# UsbAsp_IR-Gross-24.net
KiCad netlist of a schematic drawn in EAGLE
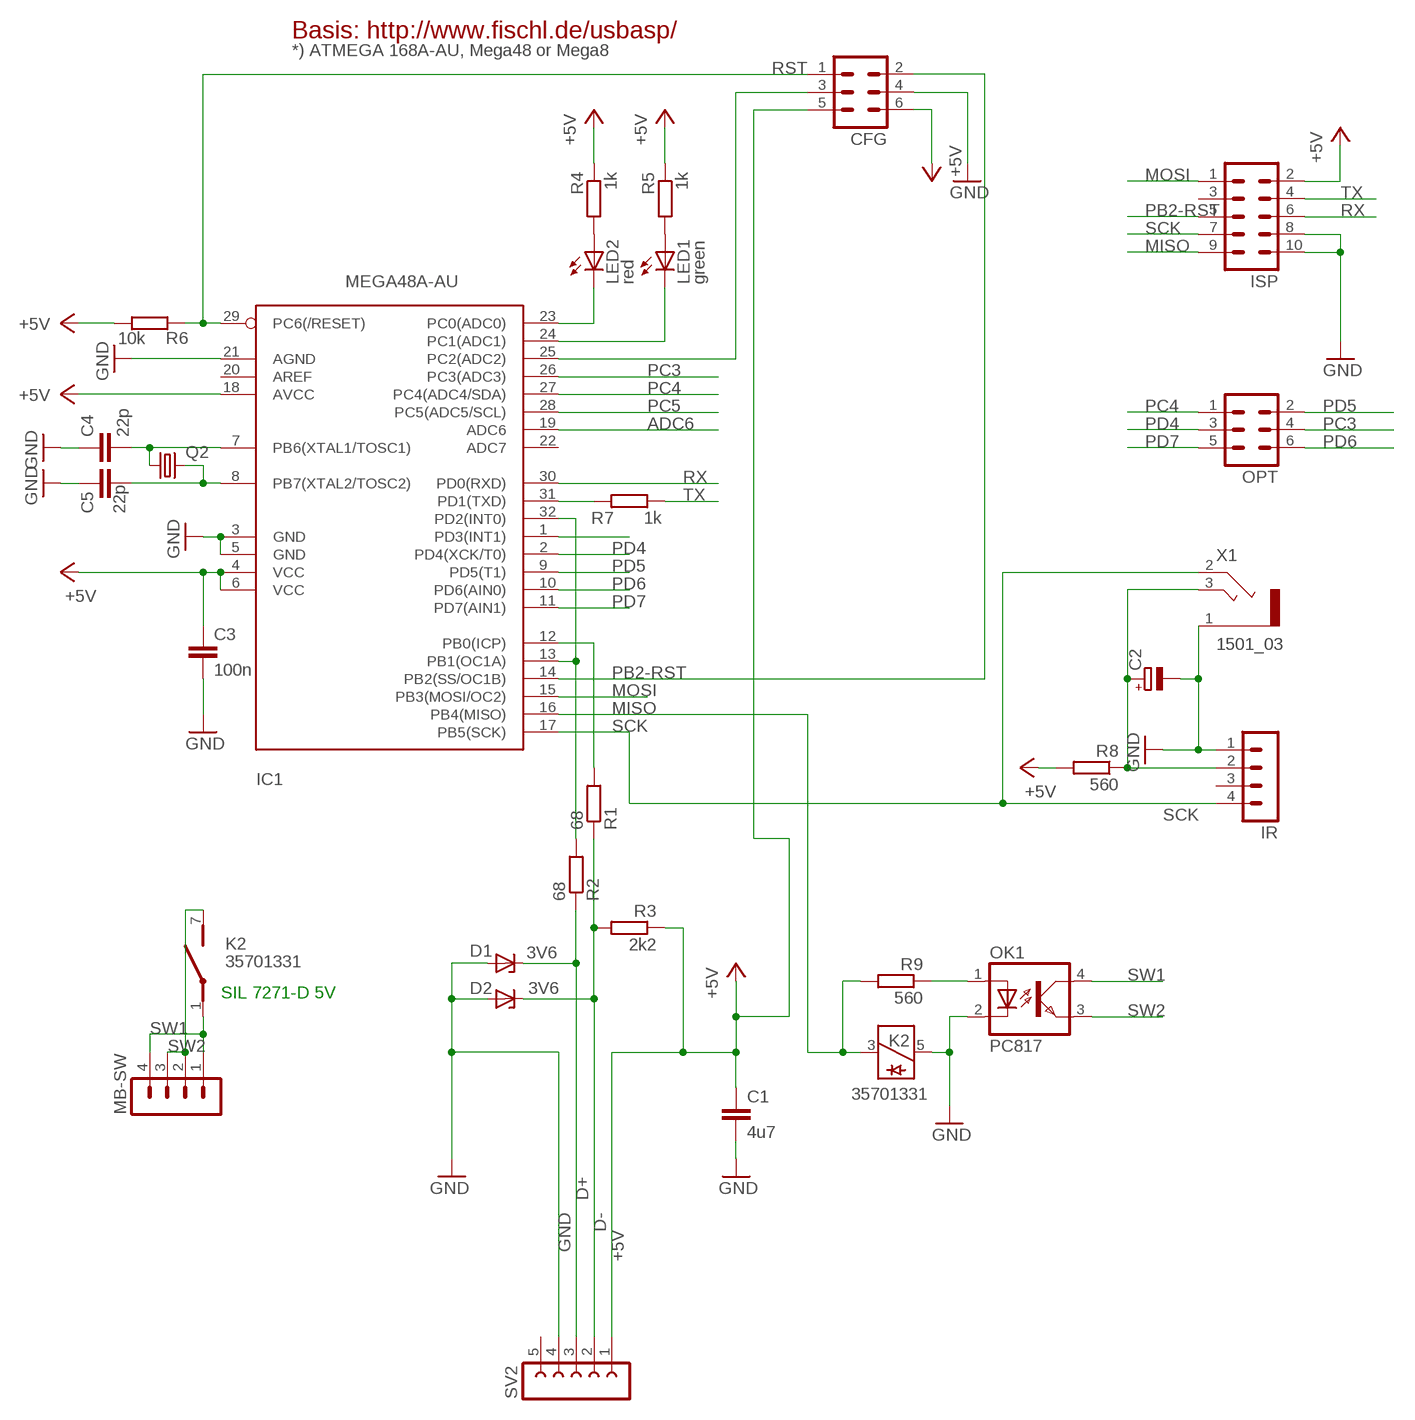
[diagram p0: schematic, sheet 1]

(export (version "E")
  (design (tool "Eeschema 10.0.6"))
  (components
    (comp (ref "C1")
      (value "4u7")
      (footprint "eagle-import:C0805")
      (libsource (lib "eagle-import") (part "C-EUC0805"))
    )
    (comp (ref "C2")
      (value "CPOL-EU085CS-1AR")
      (footprint "eagle-import:085CS_1AR")
      (libsource (lib "eagle-import") (part "CPOL-EU085CS-1AR"))
    )
    (comp (ref "C3")
      (value "100n")
      (footprint "eagle-import:C0805")
      (libsource (lib "eagle-import") (part "C-EUC0805"))
    )
    (comp (ref "C4")
      (value "22p")
      (footprint "eagle-import:C0805")
      (libsource (lib "eagle-import") (part "C-EUC0805"))
    )
    (comp (ref "C5")
      (value "22p")
      (footprint "eagle-import:C0805")
      (libsource (lib "eagle-import") (part "C-EUC0805"))
    )
    (comp (ref "CFG")
      (value "MA03-2")
      (footprint "eagle-import:MA03-2")
      (libsource (lib "eagle-import") (part "MA03-2"))
    )
    (comp (ref "D1")
      (value "3V6")
      (footprint "eagle-import:SOD80C")
      (libsource (lib "eagle-import") (part "ZENER-DIODESOD80C"))
    )
    (comp (ref "D2")
      (value "3V6")
      (footprint "eagle-import:SOD80C")
      (libsource (lib "eagle-import") (part "ZENER-DIODESOD80C"))
    )
    (comp (ref "IC1")
      (value "MEGA48A-AU")
      (footprint "eagle-import:TQFP32-08")
      (libsource (lib "eagle-import") (part "MEGA8-AI"))
    )
    (comp (ref "IR")
      (value "MA04-1")
      (footprint "eagle-import:MA04-1")
      (libsource (lib "eagle-import") (part "MA04-1"))
    )
    (comp (ref "ISP")
      (value "MA05-2")
      (footprint "eagle-import:MA05-2")
      (libsource (lib "eagle-import") (part "MA05-2"))
    )
    (comp (ref "K2")
      (value "35701331")
      (footprint "eagle-import:REED")
      (libsource (lib "eagle-import") (part "35701331"))
    )
    (comp (ref "LED1")
      (value "green")
      (footprint "eagle-import:CHIPLED_1206")
      (libsource (lib "eagle-import") (part "LEDCHIPLED_1206"))
    )
    (comp (ref "LED2")
      (value "red")
      (footprint "eagle-import:CHIPLED_1206")
      (libsource (lib "eagle-import") (part "LEDCHIPLED_1206"))
    )
    (comp (ref "MB-SW")
      (value "MA04-1")
      (footprint "eagle-import:MA04-1")
      (libsource (lib "eagle-import") (part "MA04-1"))
    )
    (comp (ref "OK1")
      (value "PC817")
      (footprint "eagle-import:DIL04")
      (fields (field (name "MPN") "PC817X4J000F"))
      (libsource (lib "eagle-import") (part "PC817"))
    )
    (comp (ref "OPT")
      (value "MA03-2")
      (footprint "eagle-import:MA03-2")
      (libsource (lib "eagle-import") (part "MA03-2"))
    )
    (comp (ref "Q2")
      (value "CRYSTALHC49UP")
      (footprint "eagle-import:HC49UP")
      (libsource (lib "eagle-import") (part "CRYSTALHC49UP"))
    )
    (comp (ref "R1")
      (value "68")
      (footprint "eagle-import:M0805")
      (libsource (lib "eagle-import") (part "R-EU_M0805"))
    )
    (comp (ref "R2")
      (value "68")
      (footprint "eagle-import:M0805")
      (libsource (lib "eagle-import") (part "R-EU_M0805"))
    )
    (comp (ref "R3")
      (value "2k2")
      (footprint "eagle-import:M0805")
      (libsource (lib "eagle-import") (part "R-EU_M0805"))
    )
    (comp (ref "R4")
      (value "1k")
      (footprint "eagle-import:M0805")
      (libsource (lib "eagle-import") (part "R-EU_M0805"))
    )
    (comp (ref "R5")
      (value "1k")
      (footprint "eagle-import:M0805")
      (libsource (lib "eagle-import") (part "R-EU_M0805"))
    )
    (comp (ref "R6")
      (value "10k")
      (footprint "eagle-import:M0805")
      (libsource (lib "eagle-import") (part "R-EU_M0805"))
    )
    (comp (ref "R7")
      (value "1k")
      (footprint "eagle-import:M0805")
      (libsource (lib "eagle-import") (part "R-EU_M0805"))
    )
    (comp (ref "R8")
      (value "560")
      (footprint "eagle-import:M0805")
      (libsource (lib "eagle-import") (part "R-EU_M0805"))
    )
    (comp (ref "R9")
      (value "560")
      (footprint "eagle-import:M0805")
      (libsource (lib "eagle-import") (part "R-EU_M0805"))
    )
    (comp (ref "SV2")
      (value "FE05W")
      (footprint "eagle-import:FE05W")
      (libsource (lib "eagle-import") (part "FE05W"))
    )
    (comp (ref "X1")
      (value "1501_03")
      (footprint "eagle-import:1501_03")
      (libsource (lib "eagle-import") (part "1501_03"))
    )
  )
  (nets
    (net (code "1") (name "+5V") (class "Default")
      (node (ref "C1") (pin "1") (pinfunction "1_1") (pintype "passive"))
      (node (ref "C3") (pin "1") (pinfunction "1_1") (pintype "passive"))
      (node (ref "CFG") (pin "5") (pinfunction "5_5") (pintype "passive"))
      (node (ref "CFG") (pin "6") (pinfunction "6_6") (pintype "passive"))
      (node (ref "IC1") (pin "18") (pinfunction "AVCC_18") (pintype "power_in"))
      (node (ref "IC1") (pin "4") (pinfunction "VCC_4") (pintype "power_in"))
      (node (ref "IC1") (pin "6") (pinfunction "VCC_6") (pintype "power_in"))
      (node (ref "ISP") (pin "2") (pinfunction "2_2") (pintype "passive"))
      (node (ref "R3") (pin "1") (pinfunction "1_1") (pintype "passive"))
      (node (ref "R4") (pin "1") (pinfunction "1_1") (pintype "passive"))
      (node (ref "R5") (pin "1") (pinfunction "1_1") (pintype "passive"))
      (node (ref "R6") (pin "1") (pinfunction "1_1") (pintype "passive"))
      (node (ref "R8") (pin "2") (pinfunction "2_2") (pintype "passive"))
      (node (ref "SV2") (pin "1") (pinfunction "1_1") (pintype "passive"))
    )
    (net (code "2") (name "/ADC6") (class "Default")
      (node (ref "IC1") (pin "19") (pinfunction "ADC6_19") (pintype "bidirectional"))
    )
    (net (code "3") (name "/D+") (class "Default")
      (node (ref "D1") (pin "C") (pinfunction "C_C") (pintype "passive"))
      (node (ref "R2") (pin "1") (pinfunction "1_1") (pintype "passive"))
      (node (ref "SV2") (pin "3") (pinfunction "3_3") (pintype "passive"))
    )
    (net (code "4") (name "/D-") (class "Default")
      (node (ref "D2") (pin "C") (pinfunction "C_C") (pintype "passive"))
      (node (ref "R1") (pin "1") (pinfunction "1_1") (pintype "passive"))
      (node (ref "R3") (pin "2") (pinfunction "2_2") (pintype "passive"))
      (node (ref "SV2") (pin "2") (pinfunction "2_2") (pintype "passive"))
    )
    (net (code "5") (name "/MISO") (class "Default")
      (node (ref "IC1") (pin "16") (pinfunction "PB4(MISO)_16") (pintype "bidirectional"))
      (node (ref "ISP") (pin "9") (pinfunction "9_9") (pintype "passive"))
      (node (ref "K2") (pin "3") (pinfunction "3_3") (pintype "passive"))
      (node (ref "R9") (pin "2") (pinfunction "2_2") (pintype "passive"))
    )
    (net (code "6") (name "/MOSI") (class "Default")
      (node (ref "IC1") (pin "15") (pinfunction "PB3(MOSI/OC2)_15") (pintype "bidirectional"))
      (node (ref "ISP") (pin "1") (pinfunction "1_1") (pintype "passive"))
    )
    (net (code "7") (name "/PB2-RST") (class "Default")
      (node (ref "CFG") (pin "2") (pinfunction "2_2") (pintype "passive"))
      (node (ref "IC1") (pin "14") (pinfunction "PB2(SS/OC1B)_14") (pintype "bidirectional"))
      (node (ref "ISP") (pin "5") (pinfunction "5_5") (pintype "passive"))
    )
    (net (code "8") (name "/PC3") (class "Default")
      (node (ref "IC1") (pin "26") (pinfunction "PC3(ADC3)_26") (pintype "bidirectional"))
      (node (ref "OPT") (pin "4") (pinfunction "4_4") (pintype "passive"))
    )
    (net (code "9") (name "/PC4") (class "Default")
      (node (ref "IC1") (pin "27") (pinfunction "PC4(ADC4/SDA)_27") (pintype "bidirectional"))
      (node (ref "OPT") (pin "1") (pinfunction "1_1") (pintype "passive"))
    )
    (net (code "10") (name "/PC5") (class "Default")
      (node (ref "IC1") (pin "28") (pinfunction "PC5(ADC5/SCL)_28") (pintype "bidirectional"))
    )
    (net (code "11") (name "/PD4") (class "Default")
      (node (ref "IC1") (pin "2") (pinfunction "PD4(XCK/T0)_2") (pintype "bidirectional"))
      (node (ref "OPT") (pin "3") (pinfunction "3_3") (pintype "passive"))
    )
    (net (code "12") (name "/PD5") (class "Default")
      (node (ref "IC1") (pin "9") (pinfunction "PD5(T1)_9") (pintype "bidirectional"))
      (node (ref "OPT") (pin "2") (pinfunction "2_2") (pintype "passive"))
    )
    (net (code "13") (name "/PD6") (class "Default")
      (node (ref "IC1") (pin "10") (pinfunction "PD6(AIN0)_10") (pintype "bidirectional"))
      (node (ref "OPT") (pin "6") (pinfunction "6_6") (pintype "passive"))
    )
    (net (code "14") (name "/PD7") (class "Default")
      (node (ref "IC1") (pin "11") (pinfunction "PD7(AIN1)_11") (pintype "bidirectional"))
      (node (ref "OPT") (pin "5") (pinfunction "5_5") (pintype "passive"))
    )
    (net (code "15") (name "/RST") (class "Default")
      (node (ref "CFG") (pin "1") (pinfunction "1_1") (pintype "passive"))
      (node (ref "IC1") (pin "29") (pinfunction "PC6(/RESET)_29") (pintype "bidirectional"))
      (node (ref "R6") (pin "2") (pinfunction "2_2") (pintype "passive"))
    )
    (net (code "16") (name "/RX") (class "Default")
      (node (ref "IC1") (pin "30") (pinfunction "PD0(RXD)_30") (pintype "bidirectional"))
      (node (ref "ISP") (pin "6") (pinfunction "6_6") (pintype "passive"))
    )
    (net (code "17") (name "/SCK") (class "Default")
      (node (ref "IC1") (pin "17") (pinfunction "PB5(SCK)_17") (pintype "bidirectional"))
      (node (ref "IR") (pin "4") (pinfunction "4_4") (pintype "passive"))
      (node (ref "ISP") (pin "7") (pinfunction "7_7") (pintype "passive"))
      (node (ref "X1") (pin "2") (pinfunction "2_2") (pintype "passive"))
    )
    (net (code "18") (name "/SW1") (class "Default")
      (node (ref "K2") (pin "1") (pinfunction "P_1") (pintype "passive"))
      (node (ref "MB-SW") (pin "1") (pinfunction "1_1") (pintype "passive"))
      (node (ref "MB-SW") (pin "4") (pinfunction "4_4") (pintype "passive"))
      (node (ref "OK1") (pin "4") (pinfunction "COL_4") (pintype "passive"))
    )
    (net (code "19") (name "/SW2") (class "Default")
      (node (ref "K2") (pin "7") (pinfunction "S_7") (pintype "passive"))
      (node (ref "MB-SW") (pin "2") (pinfunction "2_2") (pintype "passive"))
      (node (ref "MB-SW") (pin "3") (pinfunction "3_3") (pintype "passive"))
      (node (ref "OK1") (pin "3") (pinfunction "EMIT_3") (pintype "passive"))
    )
    (net (code "20") (name "/TX") (class "Default")
      (node (ref "ISP") (pin "4") (pinfunction "4_4") (pintype "passive"))
      (node (ref "R7") (pin "1") (pinfunction "1_1") (pintype "passive"))
    )
    (net (code "21") (name "GND") (class "Default")
      (node (ref "C1") (pin "2") (pinfunction "2_2") (pintype "passive"))
      (node (ref "C2") (pin "-") (pinfunction "-_-") (pintype "passive"))
      (node (ref "C3") (pin "2") (pinfunction "2_2") (pintype "passive"))
      (node (ref "C4") (pin "1") (pinfunction "1_1") (pintype "passive"))
      (node (ref "C5") (pin "1") (pinfunction "1_1") (pintype "passive"))
      (node (ref "CFG") (pin "4") (pinfunction "4_4") (pintype "passive"))
      (node (ref "D1") (pin "A") (pinfunction "A_A") (pintype "passive"))
      (node (ref "D2") (pin "A") (pinfunction "A_A") (pintype "passive"))
      (node (ref "IC1") (pin "21") (pinfunction "AGND_21") (pintype "power_in"))
      (node (ref "IC1") (pin "3") (pinfunction "GND_3") (pintype "power_in"))
      (node (ref "IC1") (pin "5") (pinfunction "GND_5") (pintype "power_in"))
      (node (ref "IR") (pin "1") (pinfunction "1_1") (pintype "passive"))
      (node (ref "ISP") (pin "10") (pinfunction "10_10") (pintype "passive"))
      (node (ref "ISP") (pin "8") (pinfunction "8_8") (pintype "passive"))
      (node (ref "K2") (pin "5") (pinfunction "5_5") (pintype "passive"))
      (node (ref "OK1") (pin "2") (pinfunction "C_2") (pintype "passive"))
      (node (ref "SV2") (pin "4") (pinfunction "4_4") (pintype "passive"))
      (node (ref "X1") (pin "1") (pinfunction "1_1") (pintype "passive"))
    )
    (net (code "22") (name "Net-(C2-Pad+)") (class "Default")
      (node (ref "C2") (pin "+") (pinfunction "+_+") (pintype "passive"))
      (node (ref "IR") (pin "2") (pinfunction "2_2") (pintype "passive"))
      (node (ref "R8") (pin "1") (pinfunction "1_1") (pintype "passive"))
      (node (ref "X1") (pin "3") (pinfunction "3_3") (pintype "passive"))
    )
    (net (code "23") (name "Net-(IC1-PB0(ICP))") (class "Default")
      (node (ref "IC1") (pin "12") (pinfunction "PB0(ICP)_12") (pintype "bidirectional"))
      (node (ref "R1") (pin "2") (pinfunction "2_2") (pintype "passive"))
    )
    (net (code "24") (name "Net-(IC1-PB1(OC1A))") (class "Default")
      (node (ref "IC1") (pin "13") (pinfunction "PB1(OC1A)_13") (pintype "bidirectional"))
      (node (ref "IC1") (pin "32") (pinfunction "PD2(INT0)_32") (pintype "bidirectional"))
      (node (ref "R2") (pin "2") (pinfunction "2_2") (pintype "passive"))
    )
    (net (code "25") (name "Net-(IC1-PB6(XTAL1{slash}TOSC1))") (class "Default")
      (node (ref "C4") (pin "2") (pinfunction "2_2") (pintype "passive"))
      (node (ref "IC1") (pin "7") (pinfunction "PB6(XTAL1/TOSC1)_7") (pintype "bidirectional"))
      (node (ref "Q2") (pin "1") (pinfunction "1_1") (pintype "passive"))
    )
    (net (code "26") (name "Net-(IC1-PB7(XTAL2{slash}TOSC2))") (class "Default")
      (node (ref "C5") (pin "2") (pinfunction "2_2") (pintype "passive"))
      (node (ref "IC1") (pin "8") (pinfunction "PB7(XTAL2/TOSC2)_8") (pintype "bidirectional"))
      (node (ref "Q2") (pin "2") (pinfunction "2_2") (pintype "passive"))
    )
    (net (code "27") (name "Net-(IC1-PC0(ADC0))") (class "Default")
      (node (ref "IC1") (pin "23") (pinfunction "PC0(ADC0)_23") (pintype "bidirectional"))
      (node (ref "LED2") (pin "C") (pinfunction "C_C") (pintype "passive"))
    )
    (net (code "28") (name "Net-(IC1-PC1(ADC1))") (class "Default")
      (node (ref "IC1") (pin "24") (pinfunction "PC1(ADC1)_24") (pintype "bidirectional"))
      (node (ref "LED1") (pin "C") (pinfunction "C_C") (pintype "passive"))
    )
    (net (code "29") (name "Net-(IC1-PC2(ADC2))") (class "Default")
      (node (ref "CFG") (pin "3") (pinfunction "3_3") (pintype "passive"))
      (node (ref "IC1") (pin "25") (pinfunction "PC2(ADC2)_25") (pintype "bidirectional"))
    )
    (net (code "30") (name "Net-(IC1-PD1(TXD))") (class "Default")
      (node (ref "IC1") (pin "31") (pinfunction "PD1(TXD)_31") (pintype "bidirectional"))
      (node (ref "R7") (pin "2") (pinfunction "2_2") (pintype "passive"))
    )
    (net (code "31") (name "Net-(LED1-PadA)") (class "Default")
      (node (ref "LED1") (pin "A") (pinfunction "A_A") (pintype "passive"))
      (node (ref "R5") (pin "2") (pinfunction "2_2") (pintype "passive"))
    )
    (net (code "32") (name "Net-(LED2-PadA)") (class "Default")
      (node (ref "LED2") (pin "A") (pinfunction "A_A") (pintype "passive"))
      (node (ref "R4") (pin "2") (pinfunction "2_2") (pintype "passive"))
    )
    (net (code "33") (name "Net-(OK1-A)") (class "Default")
      (node (ref "OK1") (pin "1") (pinfunction "A_1") (pintype "passive"))
      (node (ref "R9") (pin "1") (pinfunction "1_1") (pintype "passive"))
    )
    (net (code "34") (name "unconnected-(IC1-ADC7-Pad22)") (class "Default")
      (node (ref "IC1") (pin "22") (pinfunction "ADC7_22") (pintype "bidirectional"))
    )
    (net (code "35") (name "unconnected-(IC1-AREF-Pad20)") (class "Default")
      (node (ref "IC1") (pin "20") (pinfunction "AREF_20") (pintype "passive"))
    )
    (net (code "36") (name "unconnected-(IC1-PD3(INT1)-Pad1)") (class "Default")
      (node (ref "IC1") (pin "1") (pinfunction "PD3(INT1)_1") (pintype "bidirectional"))
    )
    (net (code "37") (name "unconnected-(IR-Pad3)") (class "Default")
      (node (ref "IR") (pin "3") (pinfunction "3_3") (pintype "passive"))
    )
    (net (code "38") (name "unconnected-(ISP-Pad3)") (class "Default")
      (node (ref "ISP") (pin "3") (pinfunction "3_3") (pintype "passive"))
    )
    (net (code "39") (name "unconnected-(SV2-Pad5)") (class "Default")
      (node (ref "SV2") (pin "5") (pinfunction "5_5") (pintype "passive"))
    )
  )
)
